# 03_NFC.net
KiCad netlist of a schematic drawn in Altium Designer
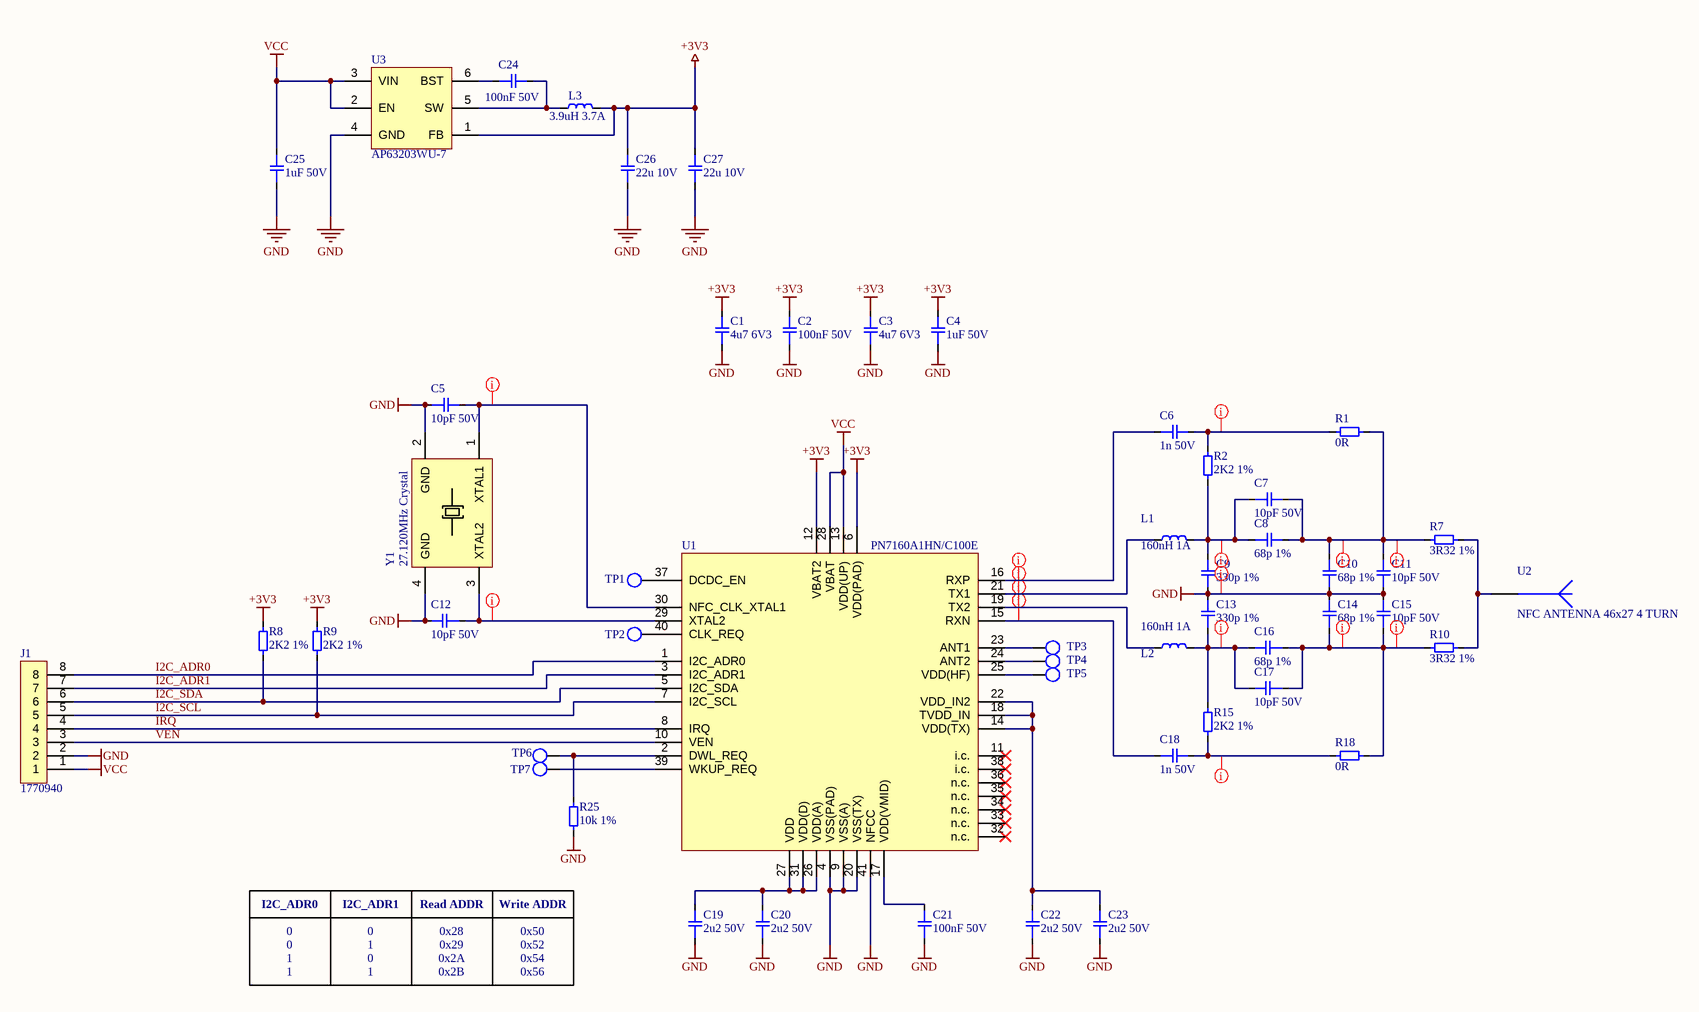
[diagram p0: 03 NFC.SchDoc]

(export (version "E")
  (design (tool "Eeschema 10.0.6"))
  (components
    (comp (ref "C1")
      (value "4u7 6V3")
      (footprint "CAPC1005X05N_MURATA_GRT")
      (description "Multilayer Ceramic Capacitors MLCC - SMD/SMT 4.7 uF 6.3 VDC 20% 0402 X6S AEC-Q200")
      (fields (field (name "MANUFACTURER") "MURATA") (field (name "MPN") "GRT155C80J475ME13D"))
      (libsource (lib "Capacitors") (part "4u7 6V3"))
    )
    (comp (ref "C2")
      (value "100nF 50V")
      (footprint "CAPC1005X05N_MURATA_GCM")
      (description "Multilayer Ceramic Capacitors MLCC - SMD/SMT 0.1 uF 50 VDC 10% 0402 X7R AEC-Q200")
      (fields (field (name "MANUFACTURER") "MURATA") (field (name "MPN") "GCM155R71H104KE02D"))
      (libsource (lib "Capacitors") (part "100nF 50V"))
    )
    (comp (ref "C3")
      (value "4u7 6V3")
      (footprint "CAPC1005X05N_MURATA_GRT")
      (description "Multilayer Ceramic Capacitors MLCC - SMD/SMT 4.7 uF 6.3 VDC 20% 0402 X6S AEC-Q200")
      (fields (field (name "MANUFACTURER") "MURATA") (field (name "MPN") "GRT155C80J475ME13D"))
      (libsource (lib "Capacitors") (part "4u7 6V3"))
    )
    (comp (ref "C4")
      (value "1uF 50V")
      (footprint "CAPC1005X05N_MURATA_GRM")
      (description "Multilayer Ceramic Capacitors MLCC - SMD/SMT 1 uF 50 VDC 10% 0402 X5R")
      (fields (field (name "MANUFACTURER") "MURATA") (field (name "MPN") "GRM155R61H105KE05D"))
      (libsource (lib "Capacitors") (part "1uF 50V"))
    )
    (comp (ref "C5")
      (value "10pF 50V")
      (footprint "CAPC1005X05N_MURATA_GRM")
      (description "Multilayer Ceramic Capacitors MLCC - SMD/SMT 10 pF 50 VDC 2% 0402 C0G (NP0)")
      (fields (field (name "MANUFACTURER") "MURATA") (field (name "MPN") "GRM1555C1H100GA01D"))
      (libsource (lib "Capacitors") (part "10pF 50V"))
    )
    (comp (ref "C6")
      (value "1n 50V")
      (footprint "CAPC1005X05N_MURATA_GCM")
      (description "Multilayer Ceramic Capacitors MLCC - SMD/SMT 1000 pF 50 VDC 2% 0402 C0G (NP0) AEC-Q200")
      (fields (field (name "MANUFACTURER") "MURATA") (field (name "MPN") "GCM1555C1H102GA16J"))
      (libsource (lib "Capacitors") (part "1n 50V"))
    )
    (comp (ref "C7")
      (value "10pF 50V")
      (footprint "CAPC1005X05N_MURATA_GRM")
      (description "Multilayer Ceramic Capacitors MLCC - SMD/SMT 10 pF 50 VDC 2% 0402 C0G (NP0)")
      (fields (field (name "MANUFACTURER") "MURATA") (field (name "MPN") "GRM1555C1H100GA01D"))
      (libsource (lib "Capacitors") (part "10pF 50V"))
    )
    (comp (ref "C8")
      (value "68p 1%")
      (footprint "CAPC1005X05N_MURATA_GCM")
      (description "Multilayer Ceramic Capacitors MLCC - SMD/SMT 0402 100VDC 68pF 5% C0G AEC-Q200")
      (fields (field (name "MANUFACTURER") "MURATA") (field (name "MPN") "GCM1555C2A680JE02D"))
      (libsource (lib "Capacitors") (part "68p 1%"))
    )
    (comp (ref "C9")
      (value "330p 1%")
      (footprint "CAPC1005X05N_MURATA_GCM")
      (description "Multilayer Ceramic Capacitors MLCC - SMD/SMT 0402 100VDC 330pF 5% C0G AEC-Q200")
      (fields (field (name "MANUFACTURER") "MURATA") (field (name "MPN") "GCM1555C2A331JE02D"))
      (libsource (lib "Capacitors") (part "330p 1%"))
    )
    (comp (ref "C10")
      (value "68p 1%")
      (footprint "CAPC1005X05N_MURATA_GCM")
      (description "Multilayer Ceramic Capacitors MLCC - SMD/SMT 0402 100VDC 68pF 5% C0G AEC-Q200")
      (fields (field (name "MANUFACTURER") "MURATA") (field (name "MPN") "GCM1555C2A680JE02D"))
      (libsource (lib "Capacitors") (part "68p 1%"))
    )
    (comp (ref "C11")
      (value "10pF 50V")
      (footprint "CAPC1005X05N_MURATA_GRM")
      (description "Multilayer Ceramic Capacitors MLCC - SMD/SMT 10 pF 50 VDC 2% 0402 C0G (NP0)")
      (fields (field (name "MANUFACTURER") "MURATA") (field (name "MPN") "GRM1555C1H100GA01D"))
      (libsource (lib "Capacitors") (part "10pF 50V"))
    )
    (comp (ref "C12")
      (value "10pF 50V")
      (footprint "CAPC1005X05N_MURATA_GRM")
      (description "Multilayer Ceramic Capacitors MLCC - SMD/SMT 10 pF 50 VDC 2% 0402 C0G (NP0)")
      (fields (field (name "MANUFACTURER") "MURATA") (field (name "MPN") "GRM1555C1H100GA01D"))
      (libsource (lib "Capacitors") (part "10pF 50V"))
    )
    (comp (ref "C13")
      (value "330p 1%")
      (footprint "CAPC1005X05N_MURATA_GCM")
      (description "Multilayer Ceramic Capacitors MLCC - SMD/SMT 0402 100VDC 330pF 5% C0G AEC-Q200")
      (fields (field (name "MANUFACTURER") "MURATA") (field (name "MPN") "GCM1555C2A331JE02D"))
      (libsource (lib "Capacitors") (part "330p 1%"))
    )
    (comp (ref "C14")
      (value "68p 1%")
      (footprint "CAPC1005X05N_MURATA_GCM")
      (description "Multilayer Ceramic Capacitors MLCC - SMD/SMT 0402 100VDC 68pF 5% C0G AEC-Q200")
      (fields (field (name "MANUFACTURER") "MURATA") (field (name "MPN") "GCM1555C2A680JE02D"))
      (libsource (lib "Capacitors") (part "68p 1%"))
    )
    (comp (ref "C15")
      (value "10pF 50V")
      (footprint "CAPC1005X05N_MURATA_GRM")
      (description "Multilayer Ceramic Capacitors MLCC - SMD/SMT 10 pF 50 VDC 2% 0402 C0G (NP0)")
      (fields (field (name "MANUFACTURER") "MURATA") (field (name "MPN") "GRM1555C1H100GA01D"))
      (libsource (lib "Capacitors") (part "10pF 50V"))
    )
    (comp (ref "C16")
      (value "68p 1%")
      (footprint "CAPC1005X05N_MURATA_GCM")
      (description "Multilayer Ceramic Capacitors MLCC - SMD/SMT 0402 100VDC 68pF 5% C0G AEC-Q200")
      (fields (field (name "MANUFACTURER") "MURATA") (field (name "MPN") "GCM1555C2A680JE02D"))
      (libsource (lib "Capacitors") (part "68p 1%"))
    )
    (comp (ref "C17")
      (value "10pF 50V")
      (footprint "CAPC1005X05N_MURATA_GRM")
      (description "Multilayer Ceramic Capacitors MLCC - SMD/SMT 10 pF 50 VDC 2% 0402 C0G (NP0)")
      (fields (field (name "MANUFACTURER") "MURATA") (field (name "MPN") "GRM1555C1H100GA01D"))
      (libsource (lib "Capacitors") (part "10pF 50V"))
    )
    (comp (ref "C18")
      (value "1n 50V")
      (footprint "CAPC1005X05N_MURATA_GCM")
      (description "Multilayer Ceramic Capacitors MLCC - SMD/SMT 1000 pF 50 VDC 2% 0402 C0G (NP0) AEC-Q200")
      (fields (field (name "MANUFACTURER") "MURATA") (field (name "MPN") "GCM1555C1H102GA16J"))
      (libsource (lib "Capacitors") (part "1n 50V"))
    )
    (comp (ref "C19")
      (value "2u2 50V")
      (footprint "CAPC1608X08N_MURATA_GRT")
      (description "Multilayer Ceramic Capacitors MLCC - SMD/SMT 2.2 uF 50 VDC 10% 0603 X5R AEC-Q200")
      (fields (field (name "MANUFACTURER") "MURATA") (field (name "MPN") "GRT188R61H225KE13D"))
      (libsource (lib "Capacitors") (part "2u2 50V"))
    )
    (comp (ref "C20")
      (value "2u2 50V")
      (footprint "CAPC1608X08N_MURATA_GRT")
      (description "Multilayer Ceramic Capacitors MLCC - SMD/SMT 2.2 uF 50 VDC 10% 0603 X5R AEC-Q200")
      (fields (field (name "MANUFACTURER") "MURATA") (field (name "MPN") "GRT188R61H225KE13D"))
      (libsource (lib "Capacitors") (part "2u2 50V"))
    )
    (comp (ref "C21")
      (value "100nF 50V")
      (footprint "CAPC1005X05N_MURATA_GCM")
      (description "Multilayer Ceramic Capacitors MLCC - SMD/SMT 0.1 uF 50 VDC 10% 0402 X7R AEC-Q200")
      (fields (field (name "MANUFACTURER") "MURATA") (field (name "MPN") "GCM155R71H104KE02D"))
      (libsource (lib "Capacitors") (part "100nF 50V"))
    )
    (comp (ref "C22")
      (value "2u2 50V")
      (footprint "CAPC1608X08N_MURATA_GRT")
      (description "Multilayer Ceramic Capacitors MLCC - SMD/SMT 2.2 uF 50 VDC 10% 0603 X5R AEC-Q200")
      (fields (field (name "MANUFACTURER") "MURATA") (field (name "MPN") "GRT188R61H225KE13D"))
      (libsource (lib "Capacitors") (part "2u2 50V"))
    )
    (comp (ref "C23")
      (value "2u2 50V")
      (footprint "CAPC1608X08N_MURATA_GRT")
      (description "Multilayer Ceramic Capacitors MLCC - SMD/SMT 2.2 uF 50 VDC 10% 0603 X5R AEC-Q200")
      (fields (field (name "MANUFACTURER") "MURATA") (field (name "MPN") "GRT188R61H225KE13D"))
      (libsource (lib "Capacitors") (part "2u2 50V"))
    )
    (comp (ref "C24")
      (value "100nF 50V")
      (footprint "CAPC1005X05N_MURATA_GCM")
      (description "Multilayer Ceramic Capacitors MLCC - SMD/SMT 0.1 uF 50 VDC 10% 0402 X7R AEC-Q200")
      (fields (field (name "MANUFACTURER") "MURATA") (field (name "MPN") "GCM155R71H104KE02D"))
      (libsource (lib "Capacitors") (part "100nF 50V"))
    )
    (comp (ref "C25")
      (value "1uF 50V")
      (footprint "CAPC1005X05N_MURATA_GRM")
      (description "Multilayer Ceramic Capacitors MLCC - SMD/SMT 1 uF 50 VDC 10% 0402 X5R")
      (fields (field (name "MANUFACTURER") "MURATA") (field (name "MPN") "GRM155R61H105KE05D"))
      (libsource (lib "Capacitors") (part "1uF 50V"))
    )
    (comp (ref "C26")
      (value "22u 10V")
      (footprint "CAPC3216X18N_MURATA_GCM")
      (description "Multilayer Ceramic Capacitors MLCC - SMD/SMT 22 uF 10 VDC 10% 1206 X7R AEC-Q200")
      (fields (field (name "MANUFACTURER") "MURATA") (field (name "MPN") "GCM31CR71A226KE02L"))
      (libsource (lib "Capacitors") (part "22u 10V"))
    )
    (comp (ref "C27")
      (value "22u 10V")
      (footprint "CAPC3216X18N_MURATA_GCM")
      (description "Multilayer Ceramic Capacitors MLCC - SMD/SMT 22 uF 10 VDC 10% 1206 X7R AEC-Q200")
      (fields (field (name "MANUFACTURER") "MURATA") (field (name "MPN") "GCM31CR71A226KE02L"))
      (libsource (lib "Capacitors") (part "22u 10V"))
    )
    (comp (ref "J1")
      (value "1770940")
      (footprint "1770940")
      (description "Fixed Terminal Blocks PTSM 0,5/ 8-2,5-H THR R32")
      (fields (field (name "MANUFACTURER") "Phoenix Contact"))
      (libsource (lib "Connectors_Wire_to_Board") (part "1770940"))
    )
    (comp (ref "L1")
      (value "160nH 1A")
      (footprint "LQW18")
      (description "RF Inductors - SMD 160nH 1000mA AEC-Q200")
      (fields (field (name "MANUFACTURER") "Murata Electronics") (field (name "MPN") "LQW18CNR16J0HD"))
      (libsource (lib "Inductors_and_Magnetics") (part "160nH 1A"))
    )
    (comp (ref "L2")
      (value "160nH 1A")
      (footprint "LQW18")
      (description "RF Inductors - SMD 160nH 1000mA AEC-Q200")
      (fields (field (name "MANUFACTURER") "Murata Electronics") (field (name "MPN") "LQW18CNR16J0HD"))
      (libsource (lib "Inductors_and_Magnetics") (part "160nH 1A"))
    )
    (comp (ref "L3")
      (value "3.9uH 3.7A")
      (footprint "IFSC2020DZER3R9N01")
      (description "Power Inductors - SMD 3.9UH 3.7A 35 MOHM SMD")
      (fields (field (name "MANUFACTURER") "Vishay / Dale") (field (name "MPN") "IFSC2020DZER3R9N01"))
      (libsource (lib "Inductors_and_Magnetics") (part "3.9uH 3.7A"))
    )
    (comp (ref "R1")
      (value "0R")
      (footprint "RESC1005X04N_YAGEO_RC")
      (description "Thick Film Resistors - SMD General Purpose Chip Resistor 0402, 0Ohms, 1%, 1/16W")
      (fields (field (name "MANUFACTURER") "YAGEO") (field (name "MPN") "RC0402FR-070RL"))
      (libsource (lib "Resistors") (part "0R"))
    )
    (comp (ref "R2")
      (value "2K2 1%")
      (footprint "RESC1005X04N_YAGEO_RC")
      (description "Thick Film Resistors - SMD General Purpose Chip Resistor 0402, 2.2kOhms, 5%, 1/16W")
      (fields (field (name "MANUFACTURER") "YAGEO") (field (name "MPN") "RC0402JR-7D2K2L"))
      (libsource (lib "Resistors") (part "2K2 1%"))
    )
    (comp (ref "R7")
      (value "3R32 1%")
      (footprint "RESC1005X04N_YAGEO_RC")
      (description "Thick Film Resistors - SMD General Purpose Chip Resistor 0402, 3.32Ohms, 1%, 1/16W")
      (fields (field (name "MANUFACTURER") "YAGEO") (field (name "MPN") "RC0402FR-073R32L"))
      (libsource (lib "Resistors") (part "3R32 1%"))
    )
    (comp (ref "R8")
      (value "2K2 1%")
      (footprint "RESC1005X04N_YAGEO_RC")
      (description "Thick Film Resistors - SMD General Purpose Chip Resistor 0402, 2.2kOhms, 5%, 1/16W")
      (fields (field (name "MANUFACTURER") "YAGEO") (field (name "MPN") "RC0402JR-7D2K2L"))
      (libsource (lib "Resistors") (part "2K2 1%"))
    )
    (comp (ref "R9")
      (value "2K2 1%")
      (footprint "RESC1005X04N_YAGEO_RC")
      (description "Thick Film Resistors - SMD General Purpose Chip Resistor 0402, 2.2kOhms, 5%, 1/16W")
      (fields (field (name "MANUFACTURER") "YAGEO") (field (name "MPN") "RC0402JR-7D2K2L"))
      (libsource (lib "Resistors") (part "2K2 1%"))
    )
    (comp (ref "R10")
      (value "3R32 1%")
      (footprint "RESC1005X04N_YAGEO_RC")
      (description "Thick Film Resistors - SMD General Purpose Chip Resistor 0402, 3.32Ohms, 1%, 1/16W")
      (fields (field (name "MANUFACTURER") "YAGEO") (field (name "MPN") "RC0402FR-073R32L"))
      (libsource (lib "Resistors") (part "3R32 1%"))
    )
    (comp (ref "R15")
      (value "2K2 1%")
      (footprint "RESC1005X04N_YAGEO_RC")
      (description "Thick Film Resistors - SMD General Purpose Chip Resistor 0402, 2.2kOhms, 5%, 1/16W")
      (fields (field (name "MANUFACTURER") "YAGEO") (field (name "MPN") "RC0402JR-7D2K2L"))
      (libsource (lib "Resistors") (part "2K2 1%"))
    )
    (comp (ref "R18")
      (value "0R")
      (footprint "RESC1005X04N_YAGEO_RC")
      (description "Thick Film Resistors - SMD General Purpose Chip Resistor 0402, 0Ohms, 1%, 1/16W")
      (fields (field (name "MANUFACTURER") "YAGEO") (field (name "MPN") "RC0402FR-070RL"))
      (libsource (lib "Resistors") (part "0R"))
    )
    (comp (ref "R25")
      (value "10k 1%")
      (footprint "RESC1005X04N_YAGEO_RC")
      (description "Thick Film Resistors - SMD General Purpose Chip Resistor 0402, 10kOhms, 1%, 1/16W")
      (fields (field (name "MANUFACTURER") "YAGEO") (field (name "MPN") "RC0402FR-0710KL"))
      (libsource (lib "Resistors") (part "10k 1%"))
    )
    (comp (ref "TP1")
      (value "Test Point 1mm")
      (footprint "Test Point 1mm")
      (libsource (lib "Miscellaneous") (part "Test Point 1mm"))
    )
    (comp (ref "TP2")
      (value "Test Point 1mm")
      (footprint "Test Point 1mm")
      (libsource (lib "Miscellaneous") (part "Test Point 1mm"))
    )
    (comp (ref "TP3")
      (value "Test Point 1mm")
      (footprint "Test Point 1mm")
      (libsource (lib "Miscellaneous") (part "Test Point 1mm"))
    )
    (comp (ref "TP4")
      (value "Test Point 1mm")
      (footprint "Test Point 1mm")
      (libsource (lib "Miscellaneous") (part "Test Point 1mm"))
    )
    (comp (ref "TP5")
      (value "Test Point 1mm")
      (footprint "Test Point 1mm")
      (libsource (lib "Miscellaneous") (part "Test Point 1mm"))
    )
    (comp (ref "TP6")
      (value "Test Point 1mm")
      (footprint "Test Point 1mm")
      (libsource (lib "Miscellaneous") (part "Test Point 1mm"))
    )
    (comp (ref "TP7")
      (value "Test Point 1mm")
      (footprint "Test Point 1mm")
      (libsource (lib "Miscellaneous") (part "Test Point 1mm"))
    )
    (comp (ref "U1")
      (value "PN7160A1HN/C100E")
      (footprint "QFN50P600X600X100-41N-D")
      (fields (field (name "MANUFACTURER") "NXP Semiconductors"))
      (libsource (lib "RF_and_Wireless") (part "PN7160A1HN/C100E_1"))
    )
    (comp (ref "U2")
      (value "NFC ANTENNA 46x27 4 TURN")
      (footprint "NFC ANTENNA 46x27 4TURN")
      (fields (field (name "MANUFACTURER") "None"))
      (libsource (lib "RF_and_Wireless") (part "NFC ANTENNA 46x27 4 TURN"))
    )
    (comp (ref "U3")
      (value "AP63203WU-7")
      (footprint "TSOT-26-6")
      (description "Switching Voltage Regulators DCDC Conv HV Buck TSOT26 T&R 3K 3V3 OUT")
      (fields (field (name "MANUFACTURER") "Diodes Incorporated"))
      (libsource (lib "Power_Management") (part "AP63203WU-7"))
    )
    (comp (ref "Y1")
      (value "27.120MHz Crystal")
      (footprint "ABM3B")
      (description "Crystals 27.12 MHZ 10PF 10PPM -40+85C")
      (fields (field (name "MPN") "ABM3B-27.120MHZ-10-D1G-T") (field (name "MANUFACTURER") "ABRACON"))
      (libsource (lib "Crystals_and_Oscillators") (part "27.120MHz Crystal"))
    )
  )
  (nets
    (net (code "1") (name "+3V3") (class "Default")
      (node (ref "C1") (pin "2") (pinfunction "2_2") (pintype "passive"))
      (node (ref "C2") (pin "2") (pinfunction "2_2") (pintype "passive"))
      (node (ref "C26") (pin "2") (pinfunction "2_2") (pintype "passive"))
      (node (ref "C27") (pin "2") (pinfunction "2_2") (pintype "passive"))
      (node (ref "C3") (pin "2") (pinfunction "2_2") (pintype "passive"))
      (node (ref "C4") (pin "2") (pinfunction "2_2") (pintype "passive"))
      (node (ref "L3") (pin "2") (pinfunction "2_2") (pintype "passive"))
      (node (ref "R8") (pin "1") (pinfunction "1_1") (pintype "passive"))
      (node (ref "R9") (pin "1") (pinfunction "1_1") (pintype "passive"))
      (node (ref "U1") (pin "12") (pinfunction "VBAT2_12") (pintype "passive"))
      (node (ref "U1") (pin "6") (pinfunction "VDD(PAD)_6") (pintype "passive"))
      (node (ref "U3") (pin "1") (pinfunction "FB_1") (pintype "passive"))
    )
    (net (code "2") (name "/I2C_ADR0") (class "Default")
      (node (ref "J1") (pin "8") (pinfunction "8_8") (pintype "passive"))
      (node (ref "U1") (pin "1") (pinfunction "I2C_ADR0_1") (pintype "passive"))
    )
    (net (code "3") (name "/I2C_ADR1") (class "Default")
      (node (ref "J1") (pin "7") (pinfunction "7_7") (pintype "passive"))
      (node (ref "U1") (pin "3") (pinfunction "I2C_ADR1_3") (pintype "passive"))
    )
    (net (code "4") (name "/I2C_SCL") (class "Default")
      (node (ref "J1") (pin "5") (pinfunction "5_5") (pintype "passive"))
      (node (ref "R9") (pin "2") (pinfunction "2_2") (pintype "passive"))
      (node (ref "U1") (pin "7") (pinfunction "I2C_SCL_7") (pintype "passive"))
    )
    (net (code "5") (name "/I2C_SDA") (class "Default")
      (node (ref "J1") (pin "6") (pinfunction "6_6") (pintype "passive"))
      (node (ref "R8") (pin "2") (pinfunction "2_2") (pintype "passive"))
      (node (ref "U1") (pin "5") (pinfunction "I2C_SDA_5") (pintype "passive"))
    )
    (net (code "6") (name "/IRQ") (class "Default")
      (node (ref "J1") (pin "4") (pinfunction "4_4") (pintype "passive"))
      (node (ref "U1") (pin "8") (pinfunction "IRQ_8") (pintype "passive"))
    )
    (net (code "7") (name "/VEN") (class "Default")
      (node (ref "J1") (pin "3") (pinfunction "3_3") (pintype "passive"))
      (node (ref "U1") (pin "10") (pinfunction "VEN_10") (pintype "passive"))
    )
    (net (code "8") (name "GND") (class "Default")
      (node (ref "C1") (pin "1") (pinfunction "1_1") (pintype "passive"))
      (node (ref "C10") (pin "1") (pinfunction "1_1") (pintype "passive"))
      (node (ref "C11") (pin "1") (pinfunction "1_1") (pintype "passive"))
      (node (ref "C12") (pin "2") (pinfunction "2_2") (pintype "passive"))
      (node (ref "C13") (pin "2") (pinfunction "2_2") (pintype "passive"))
      (node (ref "C14") (pin "2") (pinfunction "2_2") (pintype "passive"))
      (node (ref "C15") (pin "2") (pinfunction "2_2") (pintype "passive"))
      (node (ref "C19") (pin "1") (pinfunction "1_1") (pintype "passive"))
      (node (ref "C2") (pin "1") (pinfunction "1_1") (pintype "passive"))
      (node (ref "C20") (pin "1") (pinfunction "1_1") (pintype "passive"))
      (node (ref "C21") (pin "1") (pinfunction "1_1") (pintype "passive"))
      (node (ref "C22") (pin "1") (pinfunction "1_1") (pintype "passive"))
      (node (ref "C23") (pin "1") (pinfunction "1_1") (pintype "passive"))
      (node (ref "C25") (pin "1") (pinfunction "1_1") (pintype "passive"))
      (node (ref "C26") (pin "1") (pinfunction "1_1") (pintype "passive"))
      (node (ref "C27") (pin "1") (pinfunction "1_1") (pintype "passive"))
      (node (ref "C3") (pin "1") (pinfunction "1_1") (pintype "passive"))
      (node (ref "C4") (pin "1") (pinfunction "1_1") (pintype "passive"))
      (node (ref "C5") (pin "1") (pinfunction "1_1") (pintype "passive"))
      (node (ref "C9") (pin "1") (pinfunction "1_1") (pintype "passive"))
      (node (ref "J1") (pin "2") (pinfunction "2_2") (pintype "passive"))
      (node (ref "R25") (pin "1") (pinfunction "1_1") (pintype "passive"))
      (node (ref "U1") (pin "20") (pinfunction "VSS(TX)_20") (pintype "passive"))
      (node (ref "U1") (pin "4") (pinfunction "VSS(PAD)_4") (pintype "passive"))
      (node (ref "U1") (pin "41") (pinfunction "NFCC_41") (pintype "passive"))
      (node (ref "U1") (pin "9") (pinfunction "VSS(A)_9") (pintype "passive"))
      (node (ref "U3") (pin "4") (pinfunction "GND_4") (pintype "passive"))
      (node (ref "Y1") (pin "2") (pinfunction "GND_2") (pintype "passive"))
      (node (ref "Y1") (pin "4") (pinfunction "GND_4") (pintype "passive"))
    )
    (net (code "9") (name "Net-(C6-Pad2)") (class "Default")
      (node (ref "C6") (pin "2") (pinfunction "2_2") (pintype "passive"))
      (node (ref "R1") (pin "1") (pinfunction "1_1") (pintype "passive"))
      (node (ref "R2") (pin "1") (pinfunction "1_1") (pintype "passive"))
    )
    (net (code "10") (name "Net-(C7-Pad1)") (class "Default")
      (node (ref "C7") (pin "1") (pinfunction "1_1") (pintype "passive"))
      (node (ref "C8") (pin "1") (pinfunction "1_1") (pintype "passive"))
      (node (ref "C9") (pin "2") (pinfunction "2_2") (pintype "passive"))
      (node (ref "L1") (pin "2") (pinfunction "2_2") (pintype "passive"))
      (node (ref "R2") (pin "2") (pinfunction "2_2") (pintype "passive"))
    )
    (net (code "11") (name "Net-(C10-Pad2)") (class "Default")
      (node (ref "C10") (pin "2") (pinfunction "2_2") (pintype "passive"))
      (node (ref "C11") (pin "2") (pinfunction "2_2") (pintype "passive"))
      (node (ref "C7") (pin "2") (pinfunction "2_2") (pintype "passive"))
      (node (ref "C8") (pin "2") (pinfunction "2_2") (pintype "passive"))
      (node (ref "R1") (pin "2") (pinfunction "2_2") (pintype "passive"))
      (node (ref "R7") (pin "1") (pinfunction "1_1") (pintype "passive"))
    )
    (net (code "12") (name "Net-(C13-Pad1)") (class "Default")
      (node (ref "C13") (pin "1") (pinfunction "1_1") (pintype "passive"))
      (node (ref "C16") (pin "2") (pinfunction "2_2") (pintype "passive"))
      (node (ref "C17") (pin "2") (pinfunction "2_2") (pintype "passive"))
      (node (ref "L2") (pin "2") (pinfunction "2_2") (pintype "passive"))
      (node (ref "R15") (pin "1") (pinfunction "1_1") (pintype "passive"))
    )
    (net (code "13") (name "Net-(C14-Pad1)") (class "Default")
      (node (ref "C14") (pin "1") (pinfunction "1_1") (pintype "passive"))
      (node (ref "C15") (pin "1") (pinfunction "1_1") (pintype "passive"))
      (node (ref "C16") (pin "1") (pinfunction "1_1") (pintype "passive"))
      (node (ref "C17") (pin "1") (pinfunction "1_1") (pintype "passive"))
      (node (ref "R10") (pin "1") (pinfunction "1_1") (pintype "passive"))
      (node (ref "R18") (pin "2") (pinfunction "2_2") (pintype "passive"))
    )
    (net (code "14") (name "Net-(C18-Pad2)") (class "Default")
      (node (ref "C18") (pin "2") (pinfunction "2_2") (pintype "passive"))
      (node (ref "R15") (pin "2") (pinfunction "2_2") (pintype "passive"))
      (node (ref "R18") (pin "1") (pinfunction "1_1") (pintype "passive"))
    )
    (net (code "15") (name "Net-(R10-Pad2)") (class "Default")
      (node (ref "R10") (pin "2") (pinfunction "2_2") (pintype "passive"))
      (node (ref "R7") (pin "2") (pinfunction "2_2") (pintype "passive"))
      (node (ref "U2") (pin "1") (pinfunction "1_1") (pintype "passive"))
    )
    (net (code "16") (name "Net-(U1-ANT1)") (class "Default")
      (node (ref "TP3") (pin "1") (pinfunction "1_1") (pintype "passive"))
      (node (ref "U1") (pin "23") (pinfunction "ANT1_23") (pintype "passive"))
    )
    (net (code "17") (name "Net-(U1-ANT2)") (class "Default")
      (node (ref "TP4") (pin "1") (pinfunction "1_1") (pintype "passive"))
      (node (ref "U1") (pin "24") (pinfunction "ANT2_24") (pintype "passive"))
    )
    (net (code "18") (name "Net-(U1-CLK_REQ)") (class "Default")
      (node (ref "TP2") (pin "1") (pinfunction "1_1") (pintype "passive"))
      (node (ref "U1") (pin "40") (pinfunction "CLK_REQ_40") (pintype "passive"))
    )
    (net (code "19") (name "Net-(U1-DCDC_EN)") (class "Default")
      (node (ref "TP1") (pin "1") (pinfunction "1_1") (pintype "passive"))
      (node (ref "U1") (pin "37") (pinfunction "DCDC_EN_37") (pintype "passive"))
    )
    (net (code "20") (name "Net-(U1-DWL_REQ)") (class "Default")
      (node (ref "R25") (pin "2") (pinfunction "2_2") (pintype "passive"))
      (node (ref "TP6") (pin "1") (pinfunction "1_1") (pintype "passive"))
      (node (ref "U1") (pin "2") (pinfunction "DWL_REQ_2") (pintype "passive"))
    )
    (net (code "21") (name "Net-(U1-NFC_CLK_XTAL1)") (class "Default")
      (node (ref "C5") (pin "2") (pinfunction "2_2") (pintype "passive"))
      (node (ref "U1") (pin "30") (pinfunction "NFC_CLK_XTAL1_30") (pintype "passive"))
      (node (ref "Y1") (pin "1") (pinfunction "XTAL1_1") (pintype "passive"))
    )
    (net (code "22") (name "Net-(U1-RXN)") (class "Default")
      (node (ref "C18") (pin "1") (pinfunction "1_1") (pintype "passive"))
      (node (ref "U1") (pin "15") (pinfunction "RXN_15") (pintype "passive"))
    )
    (net (code "23") (name "Net-(U1-RXP)") (class "Default")
      (node (ref "C6") (pin "1") (pinfunction "1_1") (pintype "passive"))
      (node (ref "U1") (pin "16") (pinfunction "RXP_16") (pintype "passive"))
    )
    (net (code "24") (name "Net-(U1-TVDD_IN)") (class "Default")
      (node (ref "C22") (pin "2") (pinfunction "2_2") (pintype "passive"))
      (node (ref "C23") (pin "2") (pinfunction "2_2") (pintype "passive"))
      (node (ref "U1") (pin "14") (pinfunction "VDD(TX)_14") (pintype "passive"))
      (node (ref "U1") (pin "18") (pinfunction "TVDD_IN_18") (pintype "passive"))
      (node (ref "U1") (pin "22") (pinfunction "VDD_IN2_22") (pintype "passive"))
    )
    (net (code "25") (name "Net-(U1-TX1)") (class "Default")
      (node (ref "L1") (pin "1") (pinfunction "1_1") (pintype "passive"))
      (node (ref "U1") (pin "21") (pinfunction "TX1_21") (pintype "passive"))
    )
    (net (code "26") (name "Net-(U1-TX2)") (class "Default")
      (node (ref "L2") (pin "1") (pinfunction "1_1") (pintype "passive"))
      (node (ref "U1") (pin "19") (pinfunction "TX2_19") (pintype "passive"))
    )
    (net (code "27") (name "Net-(U1-VDD(A))") (class "Default")
      (node (ref "C19") (pin "2") (pinfunction "2_2") (pintype "passive"))
      (node (ref "C20") (pin "2") (pinfunction "2_2") (pintype "passive"))
      (node (ref "U1") (pin "26") (pinfunction "VDD(A)_26") (pintype "passive"))
      (node (ref "U1") (pin "27") (pinfunction "VDD_27") (pintype "passive"))
      (node (ref "U1") (pin "31") (pinfunction "VDD(D)_31") (pintype "passive"))
    )
    (net (code "28") (name "Net-(U1-VDD(HF))") (class "Default")
      (node (ref "TP5") (pin "1") (pinfunction "1_1") (pintype "passive"))
      (node (ref "U1") (pin "25") (pinfunction "VDD(HF)_25") (pintype "passive"))
    )
    (net (code "29") (name "Net-(U1-VDD(VMID))") (class "Default")
      (node (ref "C21") (pin "2") (pinfunction "2_2") (pintype "passive"))
      (node (ref "U1") (pin "17") (pinfunction "VDD(VMID)_17") (pintype "passive"))
    )
    (net (code "30") (name "Net-(U1-WKUP_REQ)") (class "Default")
      (node (ref "TP7") (pin "1") (pinfunction "1_1") (pintype "passive"))
      (node (ref "U1") (pin "39") (pinfunction "WKUP_REQ_39") (pintype "passive"))
    )
    (net (code "31") (name "Net-(U1-XTAL2)") (class "Default")
      (node (ref "C12") (pin "1") (pinfunction "1_1") (pintype "passive"))
      (node (ref "U1") (pin "29") (pinfunction "XTAL2_29") (pintype "passive"))
      (node (ref "Y1") (pin "3") (pinfunction "XTAL2_3") (pintype "passive"))
    )
    (net (code "32") (name "Net-(U3-BST)") (class "Default")
      (node (ref "C24") (pin "1") (pinfunction "1_1") (pintype "passive"))
      (node (ref "U3") (pin "6") (pinfunction "BST_6") (pintype "passive"))
    )
    (net (code "33") (name "Net-(U3-SW)") (class "Default")
      (node (ref "C24") (pin "2") (pinfunction "2_2") (pintype "passive"))
      (node (ref "L3") (pin "1") (pinfunction "1_1") (pintype "passive"))
      (node (ref "U3") (pin "5") (pinfunction "SW_5") (pintype "passive"))
    )
    (net (code "34") (name "VCC") (class "Default")
      (node (ref "C25") (pin "2") (pinfunction "2_2") (pintype "passive"))
      (node (ref "J1") (pin "1") (pinfunction "1_1") (pintype "passive"))
      (node (ref "U1") (pin "13") (pinfunction "VDD(UP)_13") (pintype "passive"))
      (node (ref "U1") (pin "28") (pinfunction "VBAT_28") (pintype "passive"))
      (node (ref "U3") (pin "2") (pinfunction "EN_2") (pintype "passive"))
      (node (ref "U3") (pin "3") (pinfunction "VIN_3") (pintype "passive"))
    )
    (net (code "35") (name "unconnected-(U1-i.c.-Pad11)") (class "Default")
      (node (ref "U1") (pin "11") (pinfunction "i.c._11") (pintype "passive+no_connect"))
    )
    (net (code "36") (name "unconnected-(U1-i.c.-Pad38)") (class "Default")
      (node (ref "U1") (pin "38") (pinfunction "i.c._38") (pintype "passive+no_connect"))
    )
    (net (code "37") (name "unconnected-(U1-n.c.-Pad32)") (class "Default")
      (node (ref "U1") (pin "32") (pinfunction "n.c._32") (pintype "passive+no_connect"))
    )
    (net (code "38") (name "unconnected-(U1-n.c.-Pad33)") (class "Default")
      (node (ref "U1") (pin "33") (pinfunction "n.c._33") (pintype "passive+no_connect"))
    )
    (net (code "39") (name "unconnected-(U1-n.c.-Pad34)") (class "Default")
      (node (ref "U1") (pin "34") (pinfunction "n.c._34") (pintype "passive+no_connect"))
    )
    (net (code "40") (name "unconnected-(U1-n.c.-Pad35)") (class "Default")
      (node (ref "U1") (pin "35") (pinfunction "n.c._35") (pintype "passive+no_connect"))
    )
    (net (code "41") (name "unconnected-(U1-n.c.-Pad36)") (class "Default")
      (node (ref "U1") (pin "36") (pinfunction "n.c._36") (pintype "passive+no_connect"))
    )
  )
)
